# bt-snes_AA.net
KiCad netlist of a schematic drawn in EAGLE
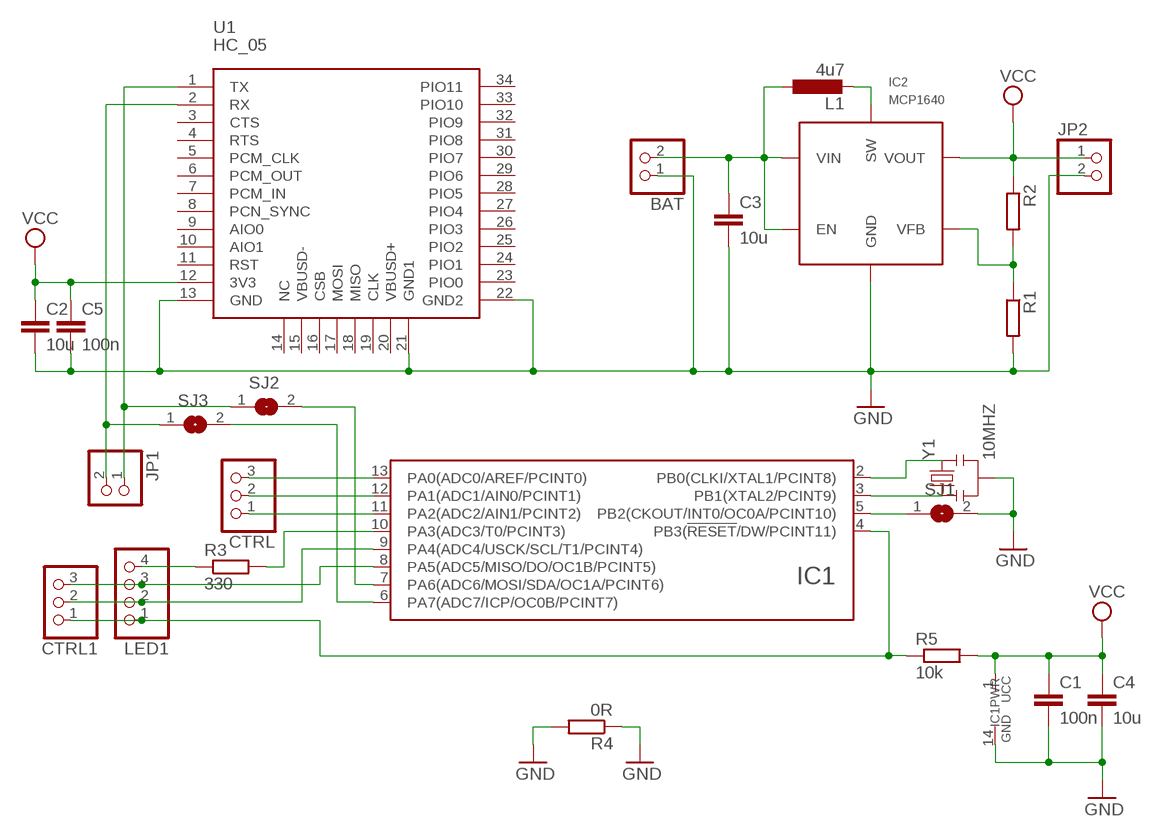
[diagram p0: schematic, sheet 1]

(export (version "E")
  (design (tool "Eeschema 10.0.6"))
  (components
    (comp (ref "BAT")
      (value "PINHD-1X2")
      (footprint "eagle-import:1X02")
      (libsource (lib "eagle-import") (part "PINHD-1X2"))
    )
    (comp (ref "C1")
      (value "100n")
      (footprint "eagle-import:C0805K")
      (libsource (lib "eagle-import") (part "C-EUC0805K"))
    )
    (comp (ref "C2")
      (value "10u")
      (footprint "eagle-import:C0805K")
      (libsource (lib "eagle-import") (part "C-EUC0805K"))
    )
    (comp (ref "C3")
      (value "10u")
      (footprint "eagle-import:C0805K")
      (libsource (lib "eagle-import") (part "C-EUC0805K"))
    )
    (comp (ref "C4")
      (value "10u")
      (footprint "eagle-import:C0805K")
      (libsource (lib "eagle-import") (part "C-EUC0805K"))
    )
    (comp (ref "C5")
      (value "100n")
      (footprint "eagle-import:C0805K")
      (libsource (lib "eagle-import") (part "C-EUC0805K"))
    )
    (comp (ref "CTRL")
      (value "PINHD-1X3")
      (footprint "eagle-import:1X03")
      (libsource (lib "eagle-import") (part "PINHD-1X3"))
    )
    (comp (ref "CTRL1")
      (value "PINHD-1X3")
      (footprint "eagle-import:1X03")
      (libsource (lib "eagle-import") (part "PINHD-1X3"))
    )
    (comp (ref "IC1")
      (value "ATTINY24/44/84-SSU")
      (footprint "eagle-import:SOIC14")
      (libsource (lib "eagle-import") (part "ATTINY24/44/84-SSU"))
    )
    (comp (ref "IC2")
      (value "MCP1640")
      (footprint "eagle-import:SOT23-6")
      (libsource (lib "eagle-import") (part "MCP1640"))
    )
    (comp (ref "JP1")
      (value "PINHD-1X2")
      (footprint "eagle-import:1X02")
      (libsource (lib "eagle-import") (part "PINHD-1X2"))
    )
    (comp (ref "JP2")
      (value "PINHD-1X2")
      (footprint "eagle-import:1X02")
      (libsource (lib "eagle-import") (part "PINHD-1X2"))
    )
    (comp (ref "L1")
      (value "4u7")
      (footprint "eagle-import:C1210")
      (libsource (lib "eagle-import") (part "L-EUL1210"))
    )
    (comp (ref "LED1")
      (value "PINHD-1X4")
      (footprint "eagle-import:1X04")
      (libsource (lib "eagle-import") (part "PINHD-1X4"))
    )
    (comp (ref "R1")
      (value "R-EU_M0805")
      (footprint "eagle-import:M0805")
      (libsource (lib "eagle-import") (part "R-EU_M0805"))
    )
    (comp (ref "R2")
      (value "R-EU_M0805")
      (footprint "eagle-import:M0805")
      (libsource (lib "eagle-import") (part "R-EU_M0805"))
    )
    (comp (ref "R3")
      (value "330")
      (footprint "eagle-import:M0805")
      (libsource (lib "eagle-import") (part "R-EU_M0805"))
    )
    (comp (ref "R4")
      (value "0R")
      (footprint "eagle-import:R1206W")
      (libsource (lib "eagle-import") (part "R-EU_R1206W"))
    )
    (comp (ref "R5")
      (value "10k")
      (footprint "eagle-import:M0805")
      (libsource (lib "eagle-import") (part "R-EU_M0805"))
    )
    (comp (ref "SJ1") (value "SJ") (footprint "eagle-import:SJ") (libsource (lib "eagle-import") (part "SJ")))
    (comp (ref "SJ2") (value "SJ") (footprint "eagle-import:SJ") (libsource (lib "eagle-import") (part "SJ")))
    (comp (ref "SJ3") (value "SJ") (footprint "eagle-import:SJ") (libsource (lib "eagle-import") (part "SJ")))
    (comp (ref "U1")
      (value "HC_05")
      (footprint "eagle-import:BLUETOOTH_SMD")
      (libsource (lib "eagle-import") (part "HC_05"))
    )
    (comp (ref "Y1")
      (value "10MHZ")
      (footprint "eagle-import:RESONATOR-SMD")
      (libsource (lib "eagle-import") (part "RESONATOR8MHZ"))
    )
  )
  (nets
    (net (code "1") (name "GND") (class "Default")
      (node (ref "BAT") (pin "1") (pinfunction "1_1") (pintype "passive"))
      (node (ref "C1") (pin "2") (pinfunction "2_2") (pintype "passive"))
      (node (ref "C2") (pin "2") (pinfunction "2_2") (pintype "passive"))
      (node (ref "C3") (pin "2") (pinfunction "2_2") (pintype "passive"))
      (node (ref "C4") (pin "2") (pinfunction "2_2") (pintype "passive"))
      (node (ref "C5") (pin "2") (pinfunction "2_2") (pintype "passive"))
      (node (ref "IC1") (pin "14") (pinfunction "GND_14") (pintype "power_in"))
      (node (ref "IC2") (pin "2") (pinfunction "GND_2") (pintype "power_in"))
      (node (ref "JP2") (pin "2") (pinfunction "2_2") (pintype "passive"))
      (node (ref "R1") (pin "2") (pinfunction "2_2") (pintype "passive"))
      (node (ref "R4") (pin "1") (pinfunction "1_1") (pintype "passive"))
      (node (ref "R4") (pin "2") (pinfunction "2_2") (pintype "passive"))
      (node (ref "SJ1") (pin "2") (pinfunction "2_2") (pintype "passive"))
      (node (ref "U1") (pin "13") (pinfunction "GND_13") (pintype "bidirectional"))
      (node (ref "U1") (pin "21") (pinfunction "GND1_21") (pintype "bidirectional"))
      (node (ref "U1") (pin "22") (pinfunction "GND2_22") (pintype "bidirectional"))
      (node (ref "Y1") (pin "2") (pinfunction "2_2") (pintype "passive"))
    )
    (net (code "2") (name "Net-(IC1A-PA0(ADC0{slash}AREF{slash}PCINT0))") (class "Default")
      (node (ref "CTRL") (pin "3") (pinfunction "3_3") (pintype "passive"))
      (node (ref "IC1") (pin "13") (pinfunction "PA0(ADC0/AREF/PCINT0)_13") (pintype "bidirectional"))
    )
    (net (code "3") (name "Net-(IC1A-PA1(ADC1{slash}AIN0{slash}PCINT1))") (class "Default")
      (node (ref "CTRL") (pin "2") (pinfunction "2_2") (pintype "passive"))
      (node (ref "IC1") (pin "12") (pinfunction "PA1(ADC1/AIN0/PCINT1)_12") (pintype "bidirectional"))
    )
    (net (code "4") (name "Net-(IC1A-PA2(ADC2{slash}AIN1{slash}PCINT2))") (class "Default")
      (node (ref "CTRL") (pin "1") (pinfunction "1_1") (pintype "passive"))
      (node (ref "IC1") (pin "11") (pinfunction "PA2(ADC2/AIN1/PCINT2)_11") (pintype "bidirectional"))
    )
    (net (code "5") (name "Net-(IC1A-PA3(ADC3{slash}T0{slash}PCINT3))") (class "Default")
      (node (ref "IC1") (pin "10") (pinfunction "PA3(ADC3/T0/PCINT3)_10") (pintype "bidirectional"))
      (node (ref "R3") (pin "2") (pinfunction "2_2") (pintype "passive"))
    )
    (net (code "6") (name "Net-(IC1A-PA4(ADC4{slash}USCK{slash}SCL{slash}T1{slash}PCINT4))") (class "Default")
      (node (ref "CTRL1") (pin "2") (pinfunction "2_2") (pintype "passive"))
      (node (ref "IC1") (pin "9") (pinfunction "PA4(ADC4/USCK/SCL/T1/PCINT4)_9") (pintype "bidirectional"))
      (node (ref "LED1") (pin "2") (pinfunction "2_2") (pintype "passive"))
    )
    (net (code "7") (name "Net-(IC1A-PA5(ADC5{slash}MISO{slash}DO{slash}OC1B{slash}PCINT5))") (class "Default")
      (node (ref "CTRL1") (pin "3") (pinfunction "3_3") (pintype "passive"))
      (node (ref "IC1") (pin "8") (pinfunction "PA5(ADC5/MISO/DO/OC1B/PCINT5)_8") (pintype "bidirectional"))
      (node (ref "LED1") (pin "3") (pinfunction "3_3") (pintype "passive"))
    )
    (net (code "8") (name "Net-(IC1A-PA6(ADC6{slash}MOSI{slash}SDA{slash}OC1A{slash}PCINT6))") (class "Default")
      (node (ref "IC1") (pin "7") (pinfunction "PA6(ADC6/MOSI/SDA/OC1A/PCINT6)_7") (pintype "bidirectional"))
      (node (ref "SJ2") (pin "2") (pinfunction "2_2") (pintype "passive"))
    )
    (net (code "9") (name "Net-(IC1A-PA7(ADC7{slash}ICP{slash}OC0B{slash}PCINT7))") (class "Default")
      (node (ref "IC1") (pin "6") (pinfunction "PA7(ADC7/ICP/OC0B/PCINT7)_6") (pintype "bidirectional"))
      (node (ref "SJ3") (pin "2") (pinfunction "2_2") (pintype "passive"))
    )
    (net (code "10") (name "Net-(IC1A-PB0(CLKI{slash}XTAL1{slash}PCINT8))") (class "Default")
      (node (ref "IC1") (pin "2") (pinfunction "PB0(CLKI/XTAL1/PCINT8)_2") (pintype "bidirectional"))
      (node (ref "Y1") (pin "3") (pinfunction "3_3") (pintype "passive"))
    )
    (net (code "11") (name "Net-(IC1A-PB1(XTAL2{slash}PCINT9))") (class "Default")
      (node (ref "IC1") (pin "3") (pinfunction "PB1(XTAL2/PCINT9)_3") (pintype "bidirectional"))
      (node (ref "Y1") (pin "1") (pinfunction "1_1") (pintype "passive"))
    )
    (net (code "12") (name "Net-(IC1A-PB2(CKOUT{slash}INT0{slash}OC0A{slash}PCINT10))") (class "Default")
      (node (ref "IC1") (pin "5") (pinfunction "PB2(CKOUT/INT0/OC0A/PCINT10)_5") (pintype "bidirectional"))
      (node (ref "SJ1") (pin "1") (pinfunction "1_1") (pintype "passive"))
    )
    (net (code "13") (name "Net-(IC1A-PB3(~{RESET}{slash}DW{slash}PCINT11))") (class "Default")
      (node (ref "CTRL1") (pin "1") (pinfunction "1_1") (pintype "passive"))
      (node (ref "IC1") (pin "4") (pinfunction "PB3(~{RESET}/DW/PCINT11)_4") (pintype "bidirectional"))
      (node (ref "LED1") (pin "1") (pinfunction "1_1") (pintype "passive"))
      (node (ref "R5") (pin "1") (pinfunction "1_1") (pintype "passive"))
    )
    (net (code "14") (name "Net-(IC2-EN)") (class "Default")
      (node (ref "BAT") (pin "2") (pinfunction "2_2") (pintype "passive"))
      (node (ref "C3") (pin "1") (pinfunction "1_1") (pintype "passive"))
      (node (ref "IC2") (pin "3") (pinfunction "EN_3") (pintype "input"))
      (node (ref "IC2") (pin "6") (pinfunction "VIN_6") (pintype "input"))
      (node (ref "L1") (pin "1") (pinfunction "1_1") (pintype "passive"))
    )
    (net (code "15") (name "Net-(IC2-SW)") (class "Default")
      (node (ref "IC2") (pin "1") (pinfunction "SW_1") (pintype "passive"))
      (node (ref "L1") (pin "2") (pinfunction "2_2") (pintype "passive"))
    )
    (net (code "16") (name "Net-(IC2-VFB)") (class "Default")
      (node (ref "IC2") (pin "4") (pinfunction "VFB_4") (pintype "input"))
      (node (ref "R1") (pin "1") (pinfunction "1_1") (pintype "passive"))
      (node (ref "R2") (pin "2") (pinfunction "2_2") (pintype "passive"))
    )
    (net (code "17") (name "Net-(LED1-Pad4)") (class "Default")
      (node (ref "LED1") (pin "4") (pinfunction "4_4") (pintype "passive"))
      (node (ref "R3") (pin "1") (pinfunction "1_1") (pintype "passive"))
    )
    (net (code "18") (name "Net-(U1-RX)") (class "Default")
      (node (ref "JP1") (pin "2") (pinfunction "2_2") (pintype "passive"))
      (node (ref "SJ3") (pin "1") (pinfunction "1_1") (pintype "passive"))
      (node (ref "U1") (pin "2") (pinfunction "RX_2") (pintype "bidirectional"))
    )
    (net (code "19") (name "Net-(U1-TX)") (class "Default")
      (node (ref "JP1") (pin "1") (pinfunction "1_1") (pintype "passive"))
      (node (ref "SJ2") (pin "1") (pinfunction "1_1") (pintype "passive"))
      (node (ref "U1") (pin "1") (pinfunction "TX_1") (pintype "bidirectional"))
    )
    (net (code "20") (name "VCC") (class "Default")
      (node (ref "C1") (pin "1") (pinfunction "1_1") (pintype "passive"))
      (node (ref "C2") (pin "1") (pinfunction "1_1") (pintype "passive"))
      (node (ref "C4") (pin "1") (pinfunction "1_1") (pintype "passive"))
      (node (ref "C5") (pin "1") (pinfunction "1_1") (pintype "passive"))
      (node (ref "IC1") (pin "1") (pinfunction "UCC_1") (pintype "power_in"))
      (node (ref "IC2") (pin "5") (pinfunction "VOUT_5") (pintype "power_in"))
      (node (ref "JP2") (pin "1") (pinfunction "1_1") (pintype "passive"))
      (node (ref "R2") (pin "1") (pinfunction "1_1") (pintype "passive"))
      (node (ref "R5") (pin "2") (pinfunction "2_2") (pintype "passive"))
      (node (ref "U1") (pin "12") (pinfunction "3V3_12") (pintype "bidirectional"))
    )
    (net (code "21") (name "unconnected-(U1-AIO0-Pad9)") (class "Default")
      (node (ref "U1") (pin "9") (pinfunction "AIO0_9") (pintype "bidirectional"))
    )
    (net (code "22") (name "unconnected-(U1-AIO1-Pad10)") (class "Default")
      (node (ref "U1") (pin "10") (pinfunction "AIO1_10") (pintype "bidirectional"))
    )
    (net (code "23") (name "unconnected-(U1-CLK-Pad19)") (class "Default")
      (node (ref "U1") (pin "19") (pinfunction "CLK_19") (pintype "bidirectional"))
    )
    (net (code "24") (name "unconnected-(U1-CSB-Pad16)") (class "Default")
      (node (ref "U1") (pin "16") (pinfunction "CSB_16") (pintype "bidirectional"))
    )
    (net (code "25") (name "unconnected-(U1-CTS-Pad3)") (class "Default")
      (node (ref "U1") (pin "3") (pinfunction "CTS_3") (pintype "bidirectional"))
    )
    (net (code "26") (name "unconnected-(U1-MISO-Pad18)") (class "Default")
      (node (ref "U1") (pin "18") (pinfunction "MISO_18") (pintype "bidirectional"))
    )
    (net (code "27") (name "unconnected-(U1-MOSI-Pad17)") (class "Default")
      (node (ref "U1") (pin "17") (pinfunction "MOSI_17") (pintype "bidirectional"))
    )
    (net (code "28") (name "unconnected-(U1-NC-Pad14)") (class "Default")
      (node (ref "U1") (pin "14") (pinfunction "NC_14") (pintype "bidirectional"))
    )
    (net (code "29") (name "unconnected-(U1-PCM_CLK-Pad5)") (class "Default")
      (node (ref "U1") (pin "5") (pinfunction "PCM_CLK_5") (pintype "bidirectional"))
    )
    (net (code "30") (name "unconnected-(U1-PCM_IN-Pad7)") (class "Default")
      (node (ref "U1") (pin "7") (pinfunction "PCM_IN_7") (pintype "bidirectional"))
    )
    (net (code "31") (name "unconnected-(U1-PCM_OUT-Pad6)") (class "Default")
      (node (ref "U1") (pin "6") (pinfunction "PCM_OUT_6") (pintype "bidirectional"))
    )
    (net (code "32") (name "unconnected-(U1-PCN_SYNC-Pad8)") (class "Default")
      (node (ref "U1") (pin "8") (pinfunction "PCN_SYNC_8") (pintype "bidirectional"))
    )
    (net (code "33") (name "unconnected-(U1-PIO0-Pad23)") (class "Default")
      (node (ref "U1") (pin "23") (pinfunction "PIO0_23") (pintype "bidirectional"))
    )
    (net (code "34") (name "unconnected-(U1-PIO1-Pad24)") (class "Default")
      (node (ref "U1") (pin "24") (pinfunction "PIO1_24") (pintype "bidirectional"))
    )
    (net (code "35") (name "unconnected-(U1-PIO2-Pad25)") (class "Default")
      (node (ref "U1") (pin "25") (pinfunction "PIO2_25") (pintype "bidirectional"))
    )
    (net (code "36") (name "unconnected-(U1-PIO3-Pad26)") (class "Default")
      (node (ref "U1") (pin "26") (pinfunction "PIO3_26") (pintype "bidirectional"))
    )
    (net (code "37") (name "unconnected-(U1-PIO4-Pad27)") (class "Default")
      (node (ref "U1") (pin "27") (pinfunction "PIO4_27") (pintype "bidirectional"))
    )
    (net (code "38") (name "unconnected-(U1-PIO5-Pad28)") (class "Default")
      (node (ref "U1") (pin "28") (pinfunction "PIO5_28") (pintype "bidirectional"))
    )
    (net (code "39") (name "unconnected-(U1-PIO6-Pad29)") (class "Default")
      (node (ref "U1") (pin "29") (pinfunction "PIO6_29") (pintype "bidirectional"))
    )
    (net (code "40") (name "unconnected-(U1-PIO7-Pad30)") (class "Default")
      (node (ref "U1") (pin "30") (pinfunction "PIO7_30") (pintype "bidirectional"))
    )
    (net (code "41") (name "unconnected-(U1-PIO8-Pad31)") (class "Default")
      (node (ref "U1") (pin "31") (pinfunction "PIO8_31") (pintype "bidirectional"))
    )
    (net (code "42") (name "unconnected-(U1-PIO9-Pad32)") (class "Default")
      (node (ref "U1") (pin "32") (pinfunction "PIO9_32") (pintype "bidirectional"))
    )
    (net (code "43") (name "unconnected-(U1-PIO10-Pad33)") (class "Default")
      (node (ref "U1") (pin "33") (pinfunction "PIO10_33") (pintype "bidirectional"))
    )
    (net (code "44") (name "unconnected-(U1-PIO11-Pad34)") (class "Default")
      (node (ref "U1") (pin "34") (pinfunction "PIO11_34") (pintype "bidirectional"))
    )
    (net (code "45") (name "unconnected-(U1-RST-Pad11)") (class "Default")
      (node (ref "U1") (pin "11") (pinfunction "RST_11") (pintype "bidirectional"))
    )
    (net (code "46") (name "unconnected-(U1-RTS-Pad4)") (class "Default")
      (node (ref "U1") (pin "4") (pinfunction "RTS_4") (pintype "bidirectional"))
    )
    (net (code "47") (name "unconnected-(U1-VBUSD+-Pad20)") (class "Default")
      (node (ref "U1") (pin "20") (pinfunction "VBUSD+_20") (pintype "bidirectional"))
    )
    (net (code "48") (name "unconnected-(U1-VBUSD--Pad15)") (class "Default")
      (node (ref "U1") (pin "15") (pinfunction "VBUSD-_15") (pintype "bidirectional"))
    )
  )
)
